# DAC.net
KiCad netlist of a schematic drawn in Altium Designer
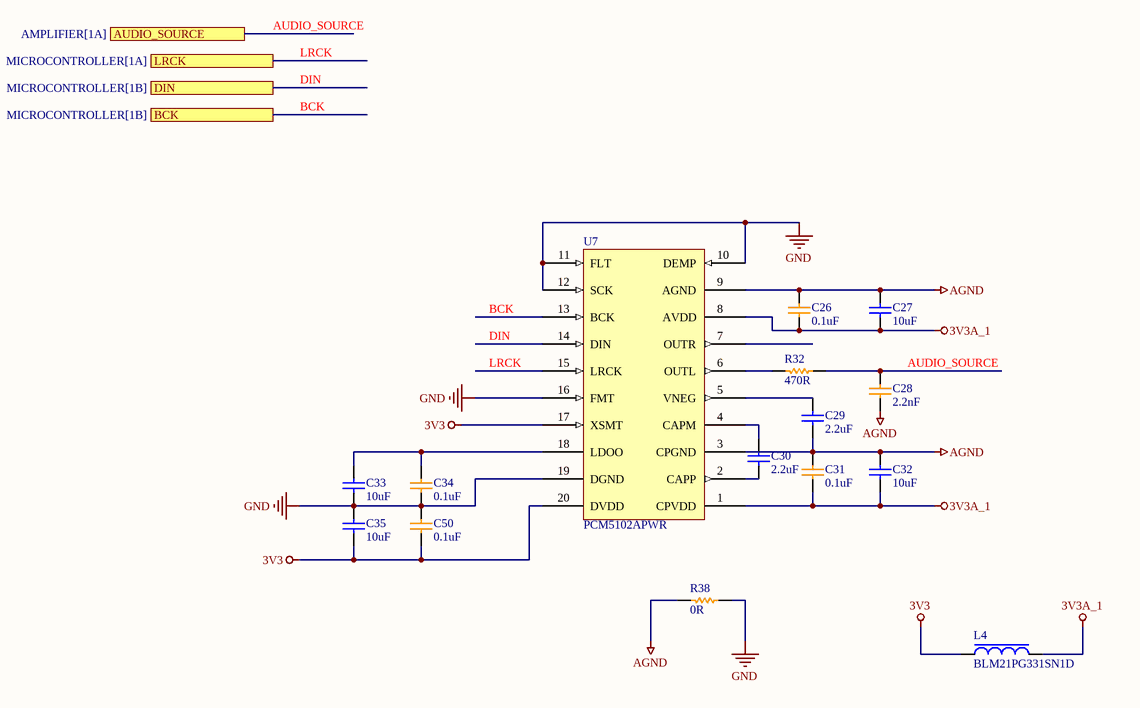
[diagram p0: DAC.SchDoc]

(export (version "E")
  (design (tool "Eeschema 10.0.6"))
  (components
    (comp (ref "C26")
      (value "0.1uF")
      (footprint "CAP-0603")
      (description "CAP CER 0.1UF 10V X7R 0603")
      (libsource (lib "Schlib1") (part "CAP-0603"))
    )
    (comp (ref "C27")
      (value "10uF")
      (footprint "CAP-0805")
      (description "CAP CER 10UF 10V X5R 0805")
      (libsource (lib "Schlib1") (part "CAP-0805"))
    )
    (comp (ref "C28")
      (value "2.2nF")
      (footprint "CAP-0603")
      (description "CAP CER 2.2NF 10V C0G/NP0 0603")
      (libsource (lib "Schlib1") (part "CAP-0603"))
    )
    (comp (ref "C29")
      (value "2.2uF")
      (footprint "CAP-0805")
      (description "CAP CER 2.2UF 10V X5R 0805")
      (libsource (lib "Schlib1") (part "CAP-0805"))
    )
    (comp (ref "C30")
      (value "2.2uF")
      (footprint "CAP-0805")
      (description "CAP CER 2.2UF 10V X5R 0805")
      (libsource (lib "Schlib1") (part "CAP-0805"))
    )
    (comp (ref "C31")
      (value "0.1uF")
      (footprint "CAP-0603")
      (description "CAP CER 0.1UF 10V X7R 0603")
      (libsource (lib "Schlib1") (part "CAP-0603"))
    )
    (comp (ref "C32")
      (value "10uF")
      (footprint "CAP-0805")
      (description "CAP CER 10UF 10V X5R 0805")
      (libsource (lib "Schlib1") (part "CAP-0805"))
    )
    (comp (ref "C33")
      (value "10uF")
      (footprint "CAP-0805")
      (description "CAP CER 10UF 16V X5R 0805")
      (libsource (lib "Schlib1") (part "CAP-0805"))
    )
    (comp (ref "C34")
      (value "0.1uF")
      (footprint "CAP-0603")
      (description "CAP CER 0.1UF 10V X7R 0603")
      (libsource (lib "Schlib1") (part "CAP-0603"))
    )
    (comp (ref "C35")
      (value "10uF")
      (footprint "CAP-0805")
      (description "CAP CER 10UF 10V X5R 0805")
      (libsource (lib "Schlib1") (part "CAP-0805"))
    )
    (comp (ref "C50")
      (value "0.1uF")
      (footprint "CAP-0603")
      (description "CAP CER 0.1UF 10V X7R 0603")
      (libsource (lib "Schlib1") (part "CAP-0603"))
    )
    (comp (ref "L4")
      (value "BLM21PG331SN1D")
      (footprint "FB-0805")
      (description "FERRITE BEAD 330 OHM 0805 1LN")
      (libsource (lib "schematic") (part "FB-0805"))
    )
    (comp (ref "R32")
      (value "470R")
      (footprint "RES-0603")
      (description "RES SMD 470 OHM 1% 1/10W 0603")
      (libsource (lib "Schlib1") (part "RES-0603"))
    )
    (comp (ref "R38")
      (value "0R")
      (footprint "RES-0603")
      (description "RES SMD 470 OHM 1% 1/10W 0603")
      (libsource (lib "Schlib1") (part "RES-0603"))
    )
    (comp (ref "U7")
      (value "PCM5102APWR")
      (footprint "20-TSSOP")
      (description "IC DAS/ADC/DAC SPECIAL 20-TSSOP")
      (libsource (lib "schematic") (part "PCM5102APWR"))
    )
  )
  (nets
    (net (code "1") (name "/AUDIO_SOURCE") (class "Default")
      (node (ref "C28") (pin "1") (pinfunction "1_1") (pintype "passive"))
      (node (ref "R32") (pin "2") (pinfunction "2_2") (pintype "passive"))
    )
    (net (code "2") (name "/BCK") (class "Default")
      (node (ref "U7") (pin "13") (pinfunction "BCK_13") (pintype "input"))
    )
    (net (code "3") (name "/DIN") (class "Default")
      (node (ref "U7") (pin "14") (pinfunction "DIN_14") (pintype "input"))
    )
    (net (code "4") (name "/LRCK") (class "Default")
      (node (ref "U7") (pin "15") (pinfunction "LRCK_15") (pintype "input"))
    )
    (net (code "5") (name "3V3") (class "Default")
      (node (ref "C35") (pin "2") (pinfunction "2_2") (pintype "passive"))
      (node (ref "C50") (pin "2") (pinfunction "2_2") (pintype "passive"))
      (node (ref "L4") (pin "1") (pinfunction "1_1") (pintype "passive"))
      (node (ref "U7") (pin "17") (pinfunction "XSMT_17") (pintype "input"))
      (node (ref "U7") (pin "20") (pinfunction "DVDD_20") (pintype "passive"))
    )
    (net (code "6") (name "3V3A_1") (class "Default")
      (node (ref "C26") (pin "1") (pinfunction "1_1") (pintype "passive"))
      (node (ref "C27") (pin "1") (pinfunction "1_1") (pintype "passive"))
      (node (ref "C31") (pin "1") (pinfunction "1_1") (pintype "passive"))
      (node (ref "C32") (pin "1") (pinfunction "1_1") (pintype "passive"))
      (node (ref "L4") (pin "2") (pinfunction "2_2") (pintype "passive"))
      (node (ref "U7") (pin "1") (pinfunction "CPVDD_1") (pintype "passive"))
      (node (ref "U7") (pin "8") (pinfunction "AVDD_8") (pintype "passive"))
    )
    (net (code "7") (name "AGND") (class "Default")
      (node (ref "C26") (pin "2") (pinfunction "2_2") (pintype "passive"))
      (node (ref "C27") (pin "2") (pinfunction "2_2") (pintype "passive"))
      (node (ref "C28") (pin "2") (pinfunction "2_2") (pintype "passive"))
      (node (ref "C29") (pin "1") (pinfunction "1_1") (pintype "passive"))
      (node (ref "C31") (pin "2") (pinfunction "2_2") (pintype "passive"))
      (node (ref "C32") (pin "2") (pinfunction "2_2") (pintype "passive"))
      (node (ref "R38") (pin "1") (pinfunction "1_1") (pintype "passive"))
      (node (ref "U7") (pin "3") (pinfunction "CPGND_3") (pintype "passive"))
      (node (ref "U7") (pin "9") (pinfunction "AGND_9") (pintype "passive"))
    )
    (net (code "8") (name "GND") (class "Default")
      (node (ref "C33") (pin "2") (pinfunction "2_2") (pintype "passive"))
      (node (ref "C34") (pin "2") (pinfunction "2_2") (pintype "passive"))
      (node (ref "C35") (pin "1") (pinfunction "1_1") (pintype "passive"))
      (node (ref "C50") (pin "1") (pinfunction "1_1") (pintype "passive"))
      (node (ref "R38") (pin "2") (pinfunction "2_2") (pintype "passive"))
      (node (ref "U7") (pin "10") (pinfunction "DEMP_10") (pintype "input"))
      (node (ref "U7") (pin "11") (pinfunction "FLT_11") (pintype "input"))
      (node (ref "U7") (pin "12") (pinfunction "SCK_12") (pintype "input"))
      (node (ref "U7") (pin "16") (pinfunction "FMT_16") (pintype "input"))
      (node (ref "U7") (pin "19") (pinfunction "DGND_19") (pintype "passive"))
    )
    (net (code "9") (name "Net-(U7-CAPM)") (class "Default")
      (node (ref "C30") (pin "2") (pinfunction "2_2") (pintype "passive"))
      (node (ref "U7") (pin "4") (pinfunction "CAPM_4") (pintype "passive"))
    )
    (net (code "10") (name "Net-(U7-CAPP)") (class "Default")
      (node (ref "C30") (pin "1") (pinfunction "1_1") (pintype "passive"))
      (node (ref "U7") (pin "2") (pinfunction "CAPP_2") (pintype "output"))
    )
    (net (code "11") (name "Net-(U7-LDOO)") (class "Default")
      (node (ref "C33") (pin "1") (pinfunction "1_1") (pintype "passive"))
      (node (ref "C34") (pin "1") (pinfunction "1_1") (pintype "passive"))
      (node (ref "U7") (pin "18") (pinfunction "LDOO_18") (pintype "passive"))
    )
    (net (code "12") (name "Net-(U7-OUTL)") (class "Default")
      (node (ref "R32") (pin "1") (pinfunction "1_1") (pintype "passive"))
      (node (ref "U7") (pin "6") (pinfunction "OUTL_6") (pintype "output"))
    )
    (net (code "13") (name "Net-(U7-VNEG)") (class "Default")
      (node (ref "C29") (pin "2") (pinfunction "2_2") (pintype "passive"))
      (node (ref "U7") (pin "5") (pinfunction "VNEG_5") (pintype "output"))
    )
    (net (code "14") (name "unconnected-(U7-OUTR-Pad7)") (class "Default")
      (node (ref "U7") (pin "7") (pinfunction "OUTR_7") (pintype "output"))
    )
  )
)
